# LNA.net
KiCad netlist of a schematic drawn in Altium Designer
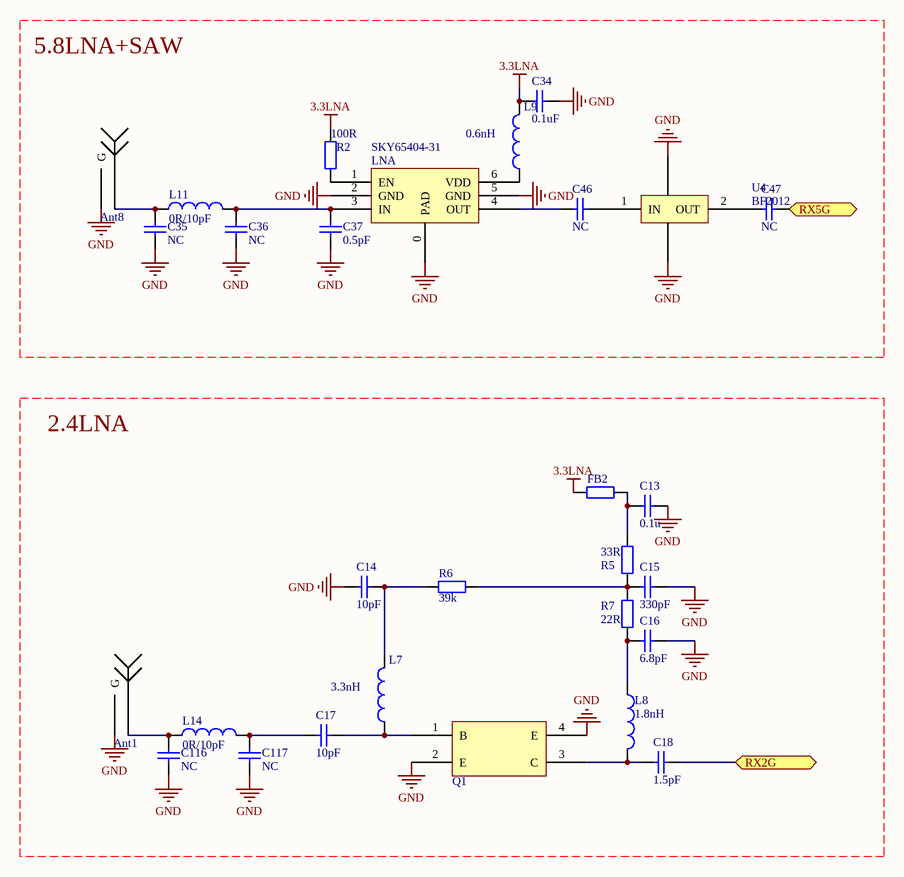
[diagram p0: LNA.SchDoc]

(export (version "E")
  (design (tool "Eeschema 10.0.6"))
  (components
    (comp (ref "Ant1") (value "Antenna") (footprint "SMA-2") (libsource (lib "RTC6705") (part "Antenna")))
    (comp (ref "Ant8") (value "Antenna") (footprint "SMA-2") (libsource (lib "RTC6705") (part "Antenna")))
    (comp (ref "C13")
      (value "0.1u")
      (footprint "0402")
      (description "Capacitor")
      (fields (field (name "Comment") "Cap") (field (name "PUBLISHER") "Altium Limited"))
      (libsource (lib "RTC6705") (part "Cap"))
    )
    (comp (ref "C14")
      (value "10pF")
      (footprint "0402")
      (description "Capacitor")
      (fields (field (name "Comment") "Cap") (field (name "PUBLISHER") "Altium Limited"))
      (libsource (lib "RTC6705") (part "Cap"))
    )
    (comp (ref "C15")
      (value "330pF")
      (footprint "0402")
      (description "Capacitor")
      (fields (field (name "Comment") "Cap") (field (name "PUBLISHER") "Altium Limited"))
      (libsource (lib "RTC6705") (part "Cap"))
    )
    (comp (ref "C16")
      (value "6.8pF")
      (footprint "0402")
      (description "Capacitor")
      (fields (field (name "Comment") "Cap") (field (name "PUBLISHER") "Altium Limited"))
      (libsource (lib "RTC6705") (part "Cap"))
    )
    (comp (ref "C17")
      (value "10pF")
      (footprint "0402")
      (description "Capacitor")
      (fields (field (name "Comment") "Cap") (field (name "PUBLISHER") "Altium Limited"))
      (libsource (lib "RTC6705") (part "Cap"))
    )
    (comp (ref "C18")
      (value "1.5pF")
      (footprint "0402")
      (description "Capacitor")
      (fields (field (name "Comment") "Cap") (field (name "PUBLISHER") "Altium Limited"))
      (libsource (lib "RTC6705") (part "Cap"))
    )
    (comp (ref "C34")
      (value "0.1uF")
      (footprint "0402")
      (description "Capacitor")
      (fields (field (name "Comment") "Cap") (field (name "PUBLISHER") "Altium Limited"))
      (libsource (lib "RTC6705") (part "Cap"))
    )
    (comp (ref "C35")
      (value "NC")
      (footprint "0402")
      (description "Capacitor")
      (fields (field (name "Comment") "Cap") (field (name "PUBLISHER") "Altium Limited"))
      (libsource (lib "RTC6705") (part "Cap"))
    )
    (comp (ref "C36")
      (value "NC")
      (footprint "0402")
      (description "Capacitor")
      (fields (field (name "Comment") "Cap") (field (name "PUBLISHER") "Altium Limited"))
      (libsource (lib "RTC6705") (part "Cap"))
    )
    (comp (ref "C37")
      (value "0.5pF")
      (footprint "0402")
      (description "Capacitor")
      (fields (field (name "Comment") "Cap") (field (name "PUBLISHER") "Altium Limited"))
      (libsource (lib "RTC6705") (part "Cap"))
    )
    (comp (ref "C46")
      (value "NC")
      (footprint "0402")
      (description "Capacitor")
      (fields (field (name "Comment") "Cap") (field (name "PUBLISHER") "Altium Limited"))
      (libsource (lib "RTC6705") (part "Cap"))
    )
    (comp (ref "C47")
      (value "NC")
      (footprint "0402")
      (description "Capacitor")
      (fields (field (name "Comment") "Cap") (field (name "PUBLISHER") "Altium Limited"))
      (libsource (lib "RTC6705") (part "Cap"))
    )
    (comp (ref "C116")
      (value "NC")
      (footprint "0402")
      (description "Capacitor")
      (fields (field (name "Comment") "Cap") (field (name "PUBLISHER") "Altium Limited"))
      (libsource (lib "RTC6705") (part "Cap"))
    )
    (comp (ref "C117")
      (value "NC")
      (footprint "0402")
      (description "Capacitor")
      (fields (field (name "Comment") "Cap") (field (name "PUBLISHER") "Altium Limited"))
      (libsource (lib "RTC6705") (part "Cap"))
    )
    (comp (ref "FB2")
      (value "Res2")
      (footprint "0402")
      (description "Resistor")
      (fields (field (name "PUBLISHER") "Altium Limited"))
      (libsource (lib "") (part "Res2_1"))
    )
    (comp (ref "L7")
      (value "3.3nH")
      (footprint "0402")
      (description "Inductor")
      (fields (field (name "PUBLISHER") "Altium Limited"))
      (libsource (lib "Miscellaneous Devices") (part "Inductor"))
    )
    (comp (ref "L8")
      (value "1.8nH")
      (footprint "0402")
      (description "Inductor")
      (fields (field (name "PUBLISHER") "Altium Limited"))
      (libsource (lib "Miscellaneous Devices") (part "Inductor"))
    )
    (comp (ref "L9")
      (value "0.6nH")
      (footprint "0402")
      (description "Inductor")
      (fields (field (name "PUBLISHER") "Altium Limited"))
      (libsource (lib "Miscellaneous Devices") (part "Inductor"))
    )
    (comp (ref "L11")
      (value "0R/10pF")
      (footprint "0402")
      (description "Inductor")
      (fields (field (name "PUBLISHER") "Altium Limited"))
      (libsource (lib "Miscellaneous Devices") (part "Inductor"))
    )
    (comp (ref "L14")
      (value "0R/10pF")
      (footprint "0402")
      (description "Inductor")
      (fields (field (name "PUBLISHER") "Altium Limited"))
      (libsource (lib "Miscellaneous Devices") (part "Inductor"))
    )
    (comp (ref "LNA")
      (value "SKY65404-31")
      (footprint "SKY65404-31")
      (libsource (lib "BK5811") (part "SKY65404-31"))
    )
    (comp (ref "Q1") (value "RF_BJT") (footprint "SOT343-4(RF)") (libsource (lib "WifiGain") (part "RF_BJT")))
    (comp (ref "R2")
      (value "100R")
      (footprint "0402")
      (description "Resistor")
      (fields (field (name "Comment") "Res2") (field (name "PUBLISHER") "Altium Limited"))
      (libsource (lib "RTC6705") (part "Res2"))
    )
    (comp (ref "R5")
      (value "33R")
      (footprint "0402")
      (description "Resistor")
      (fields (field (name "Comment") "Res2") (field (name "PUBLISHER") "Altium Limited"))
      (libsource (lib "RTC6705") (part "Res2"))
    )
    (comp (ref "R6")
      (value "39k")
      (footprint "0402")
      (description "Resistor")
      (fields (field (name "Comment") "Res2") (field (name "PUBLISHER") "Altium Limited"))
      (libsource (lib "") (part "Res2_2"))
    )
    (comp (ref "R7")
      (value "22R")
      (footprint "0402")
      (description "Resistor")
      (fields (field (name "Comment") "Res2") (field (name "PUBLISHER") "Altium Limited"))
      (libsource (lib "") (part "Res2_3"))
    )
    (comp (ref "U4") (value "BF2012") (footprint "LFB2H5") (libsource (lib "RTC6705") (part "BF2012")))
  )
  (nets
    (net (code "1") (name "/RX2G") (class "Default")
      (node (ref "C18") (pin "1") (pinfunction "1_1") (pintype "passive"))
    )
    (net (code "2") (name "/RX5G") (class "Default")
      (node (ref "C47") (pin "2") (pinfunction "2_2") (pintype "passive"))
    )
    (net (code "3") (name "3.3LNA") (class "Default")
      (node (ref "C34") (pin "2") (pinfunction "2_2") (pintype "passive"))
      (node (ref "FB2") (pin "1") (pinfunction "1_1") (pintype "passive"))
      (node (ref "L9") (pin "2") (pinfunction "2_2") (pintype "passive"))
      (node (ref "R2") (pin "2") (pinfunction "2_2") (pintype "passive"))
    )
    (net (code "4") (name "GND") (class "Default")
      (node (ref "Ant1") (pin "GND") (pinfunction "G_GND") (pintype "passive"))
      (node (ref "Ant8") (pin "GND") (pinfunction "G_GND") (pintype "passive"))
      (node (ref "C116") (pin "1") (pinfunction "1_1") (pintype "passive"))
      (node (ref "C117") (pin "1") (pinfunction "1_1") (pintype "passive"))
      (node (ref "C13") (pin "1") (pinfunction "1_1") (pintype "passive"))
      (node (ref "C14") (pin "2") (pinfunction "2_2") (pintype "passive"))
      (node (ref "C15") (pin "2") (pinfunction "2_2") (pintype "passive"))
      (node (ref "C16") (pin "1") (pinfunction "1_1") (pintype "passive"))
      (node (ref "C34") (pin "1") (pinfunction "1_1") (pintype "passive"))
      (node (ref "C35") (pin "1") (pinfunction "1_1") (pintype "passive"))
      (node (ref "C36") (pin "1") (pinfunction "1_1") (pintype "passive"))
      (node (ref "C37") (pin "1") (pinfunction "1_1") (pintype "passive"))
      (node (ref "LNA") (pin "0") (pinfunction "PAD_0") (pintype "passive"))
      (node (ref "LNA") (pin "2") (pinfunction "GND_2") (pintype "passive"))
      (node (ref "LNA") (pin "5") (pinfunction "GND_5") (pintype "passive"))
      (node (ref "Q1") (pin "2") (pinfunction "E_2") (pintype "passive"))
      (node (ref "Q1") (pin "4") (pinfunction "E_4") (pintype "passive"))
      (node (ref "U4") (pin "0") (pinfunction "GND_0") (pintype "passive"))
    )
    (net (code "5") (name "Net-(Ant1-Pad1)") (class "Default")
      (node (ref "Ant1") (pin "1") (pinfunction "1_1") (pintype "passive"))
      (node (ref "C116") (pin "2") (pinfunction "2_2") (pintype "passive"))
      (node (ref "L14") (pin "1") (pinfunction "1_1") (pintype "passive"))
    )
    (net (code "6") (name "Net-(Ant8-Pad1)") (class "Default")
      (node (ref "Ant8") (pin "1") (pinfunction "1_1") (pintype "passive"))
      (node (ref "C35") (pin "2") (pinfunction "2_2") (pintype "passive"))
      (node (ref "L11") (pin "1") (pinfunction "1_1") (pintype "passive"))
    )
    (net (code "7") (name "Net-(C13-Pad2)") (class "Default")
      (node (ref "C13") (pin "2") (pinfunction "2_2") (pintype "passive"))
      (node (ref "FB2") (pin "2") (pinfunction "2_2") (pintype "passive"))
      (node (ref "R5") (pin "2") (pinfunction "2_2") (pintype "passive"))
    )
    (net (code "8") (name "Net-(C14-Pad1)") (class "Default")
      (node (ref "C14") (pin "1") (pinfunction "1_1") (pintype "passive"))
      (node (ref "L7") (pin "2") (pinfunction "2_2") (pintype "passive"))
      (node (ref "R6") (pin "2") (pinfunction "2_2") (pintype "passive"))
    )
    (net (code "9") (name "Net-(C15-Pad1)") (class "Default")
      (node (ref "C15") (pin "1") (pinfunction "1_1") (pintype "passive"))
      (node (ref "R5") (pin "1") (pinfunction "1_1") (pintype "passive"))
      (node (ref "R6") (pin "1") (pinfunction "1_1") (pintype "passive"))
      (node (ref "R7") (pin "1") (pinfunction "1_1") (pintype "passive"))
    )
    (net (code "10") (name "Net-(C16-Pad2)") (class "Default")
      (node (ref "C16") (pin "2") (pinfunction "2_2") (pintype "passive"))
      (node (ref "L8") (pin "1") (pinfunction "1_1") (pintype "passive"))
      (node (ref "R7") (pin "2") (pinfunction "2_2") (pintype "passive"))
    )
    (net (code "11") (name "Net-(C117-Pad2)") (class "Default")
      (node (ref "C117") (pin "2") (pinfunction "2_2") (pintype "passive"))
      (node (ref "C17") (pin "2") (pinfunction "2_2") (pintype "passive"))
      (node (ref "L14") (pin "2") (pinfunction "2_2") (pintype "passive"))
    )
    (net (code "12") (name "Net-(LNA-EN)") (class "Default")
      (node (ref "LNA") (pin "1") (pinfunction "EN_1") (pintype "passive"))
      (node (ref "R2") (pin "1") (pinfunction "1_1") (pintype "passive"))
    )
    (net (code "13") (name "Net-(LNA-IN)") (class "Default")
      (node (ref "C36") (pin "2") (pinfunction "2_2") (pintype "passive"))
      (node (ref "C37") (pin "2") (pinfunction "2_2") (pintype "passive"))
      (node (ref "L11") (pin "2") (pinfunction "2_2") (pintype "passive"))
      (node (ref "LNA") (pin "3") (pinfunction "IN_3") (pintype "passive"))
    )
    (net (code "14") (name "Net-(LNA-OUT)") (class "Default")
      (node (ref "C46") (pin "1") (pinfunction "1_1") (pintype "passive"))
      (node (ref "LNA") (pin "4") (pinfunction "OUT_4") (pintype "passive"))
    )
    (net (code "15") (name "Net-(LNA-VDD)") (class "Default")
      (node (ref "L9") (pin "1") (pinfunction "1_1") (pintype "passive"))
      (node (ref "LNA") (pin "6") (pinfunction "VDD_6") (pintype "passive"))
    )
    (net (code "16") (name "Net-(Q1-B)") (class "Default")
      (node (ref "C17") (pin "1") (pinfunction "1_1") (pintype "passive"))
      (node (ref "L7") (pin "1") (pinfunction "1_1") (pintype "passive"))
      (node (ref "Q1") (pin "1") (pinfunction "B_1") (pintype "passive"))
    )
    (net (code "17") (name "Net-(Q1-C)") (class "Default")
      (node (ref "C18") (pin "2") (pinfunction "2_2") (pintype "passive"))
      (node (ref "L8") (pin "2") (pinfunction "2_2") (pintype "passive"))
      (node (ref "Q1") (pin "3") (pinfunction "C_3") (pintype "passive"))
    )
    (net (code "18") (name "Net-(U4-IN)") (class "Default")
      (node (ref "C46") (pin "2") (pinfunction "2_2") (pintype "passive"))
      (node (ref "U4") (pin "1") (pinfunction "IN_1") (pintype "passive"))
    )
    (net (code "19") (name "Net-(U4-OUT)") (class "Default")
      (node (ref "C47") (pin "1") (pinfunction "1_1") (pintype "passive"))
      (node (ref "U4") (pin "2") (pinfunction "OUT_2") (pintype "passive"))
    )
  )
)
